# TopLevel.net
KiCad netlist of a schematic drawn in Altium Designer
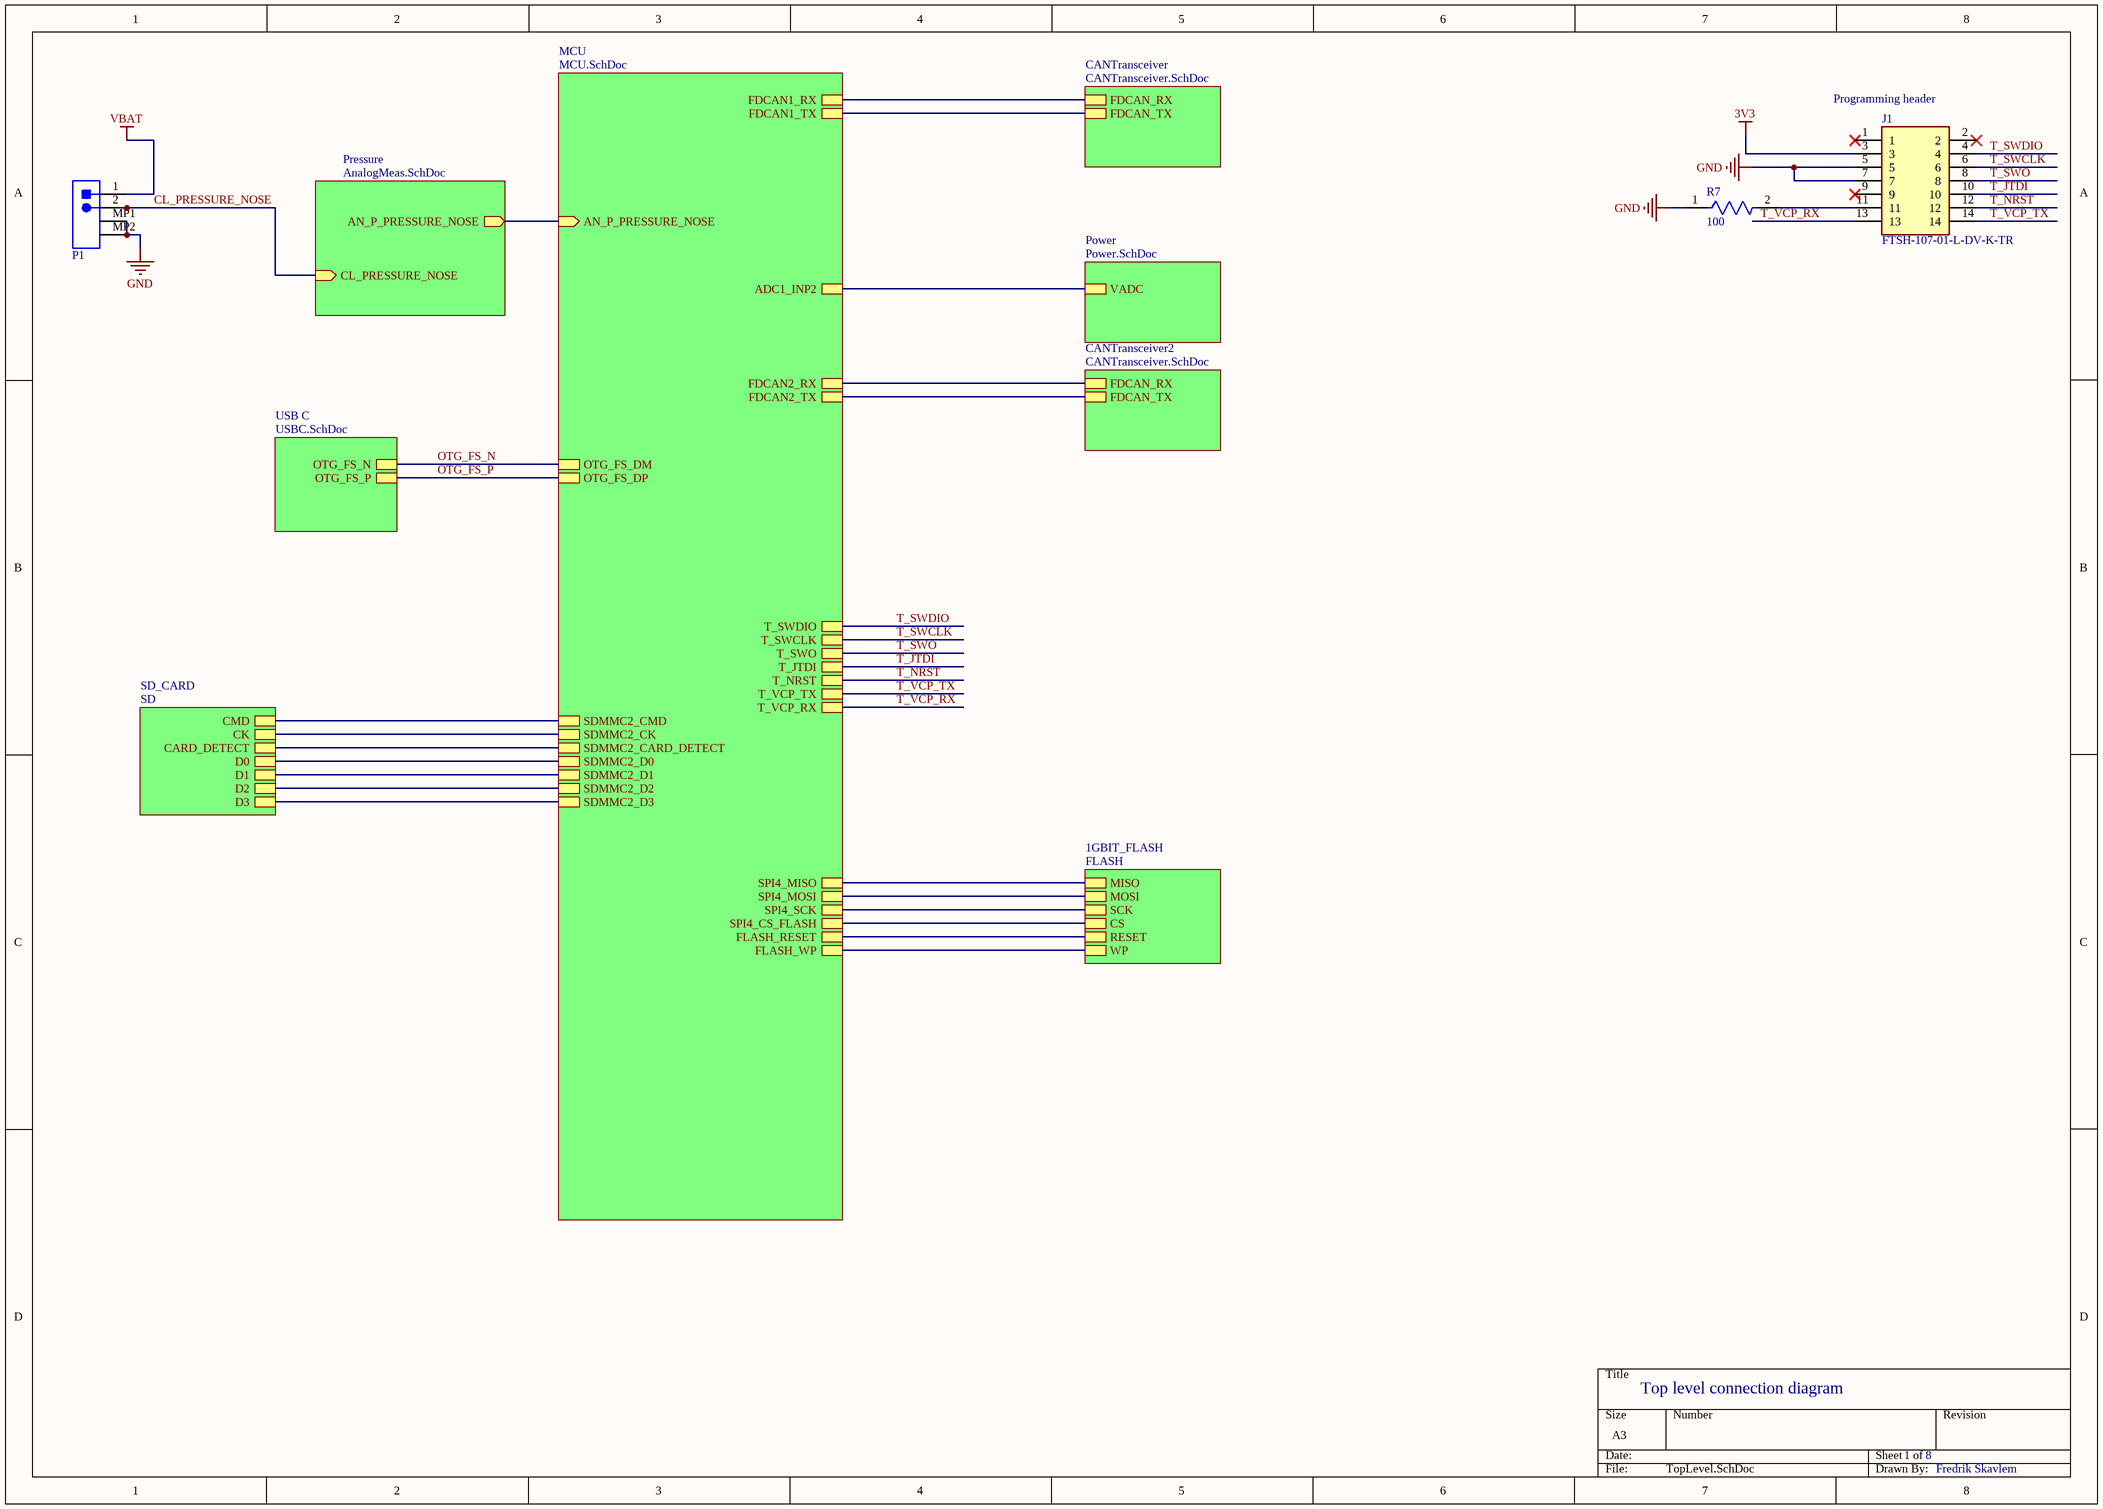
[diagram p0: TopLevel.SchDoc]

(export (version "E")
  (design (tool "Eeschema 10.0.6"))
  (components
    (comp (ref "J1")
      (value "FTSH-107-01-L-DV-K-TR")
      (footprint "SamacSys:FTSH10701LDVKTR")
      (description "Connector")
      (fields (field (name "MOUSER PART NUMBER") "200-FTSH10701LDVKTR"))
      (libsource (lib "*") (part "FTSH-107-01-L-DV-K-TR"))
    )
    (comp (ref "P1")
      (value "S2B-PH-SM4-TB(LF)(SN)")
      (footprint "JST- S2B-PH-SM4-TB(LF)(SN)-2_V")
      (description "Male Header, Pitch 2 mm, 1 x 2 Position, Height 5.5 mm, -25 to 85 degC, RoHS, Tape and Reel")
      (fields (field (name "MANUFACTURER") "JST"))
      (libsource (lib "UiS Aerospace") (part "CN-1P-2M-R2"))
    )
    (comp (ref "R7")
      (value "100")
      (footprint "FP-RT0603-MFG")
      (description "RT0603 100Ω 0.1W 50 ppm/°C 1.00% RT0603FRE07100RL")
      (fields
        (field (name "OCTOPART") "https://octopart.com/rt0603fre10100rl-yageo-22252409")
        (field (name "TOLERANCE") "0.01")
      )
      (libsource (lib "Altium Content Vault") (part "1029c3af85768c4190bb7ad29bc67b5"))
    )
  )
  (nets
    (net (code "5") (name "/CL_PRESSURE_NOSE") (class "Default")
      (node (ref "P1") (pin "2") (pinfunction "2_2") (pintype "passive"))
    )
    (net (code "23") (name "/T_JTDI") (class "Default")
      (node (ref "J1") (pin "10") (pinfunction "10_10") (pintype "passive"))
    )
    (net (code "24") (name "/T_NRST") (class "Default")
      (node (ref "J1") (pin "12") (pinfunction "12_12") (pintype "passive"))
    )
    (net (code "25") (name "/T_SWCLK") (class "Default")
      (node (ref "J1") (pin "6") (pinfunction "6_6") (pintype "passive"))
    )
    (net (code "26") (name "/T_SWDIO") (class "Default")
      (node (ref "J1") (pin "4") (pinfunction "4_4") (pintype "passive"))
    )
    (net (code "27") (name "/T_SWO") (class "Default")
      (node (ref "J1") (pin "8") (pinfunction "8_8") (pintype "passive"))
    )
    (net (code "28") (name "/T_VCP_RX") (class "Default")
      (node (ref "J1") (pin "13") (pinfunction "13_13") (pintype "passive"))
    )
    (net (code "29") (name "/T_VCP_TX") (class "Default")
      (node (ref "J1") (pin "14") (pinfunction "14_14") (pintype "passive"))
    )
    (net (code "30") (name "3V3") (class "Default")
      (node (ref "J1") (pin "3") (pinfunction "3_3") (pintype "passive"))
    )
    (net (code "31") (name "GND") (class "Default")
      (node (ref "J1") (pin "5") (pinfunction "5_5") (pintype "passive"))
      (node (ref "J1") (pin "7") (pinfunction "7_7") (pintype "passive"))
      (node (ref "P1") (pin "MP1") (pinfunction "MP1_MP1") (pintype "passive"))
      (node (ref "P1") (pin "MP2") (pinfunction "MP2_MP2") (pintype "passive"))
      (node (ref "R7") (pin "1") (pinfunction "1_1") (pintype "passive"))
    )
    (net (code "32") (name "Net-(J1-Pad11)") (class "Default")
      (node (ref "J1") (pin "11") (pinfunction "11_11") (pintype "passive"))
      (node (ref "R7") (pin "2") (pinfunction "2_2") (pintype "passive"))
    )
    (net (code "33") (name "VBAT") (class "Default")
      (node (ref "P1") (pin "1") (pinfunction "1_1") (pintype "passive"))
    )
    (net (code "34") (name "unconnected-(J1-Pad1)") (class "Default")
      (node (ref "J1") (pin "1") (pinfunction "1_1") (pintype "passive+no_connect"))
    )
    (net (code "35") (name "unconnected-(J1-Pad2)") (class "Default")
      (node (ref "J1") (pin "2") (pinfunction "2_2") (pintype "passive+no_connect"))
    )
    (net (code "36") (name "unconnected-(J1-Pad9)") (class "Default")
      (node (ref "J1") (pin "9") (pinfunction "9_9") (pintype "passive+no_connect"))
    )
  )
)
